# Main.net
KiCad netlist of a schematic drawn in Altium Designer
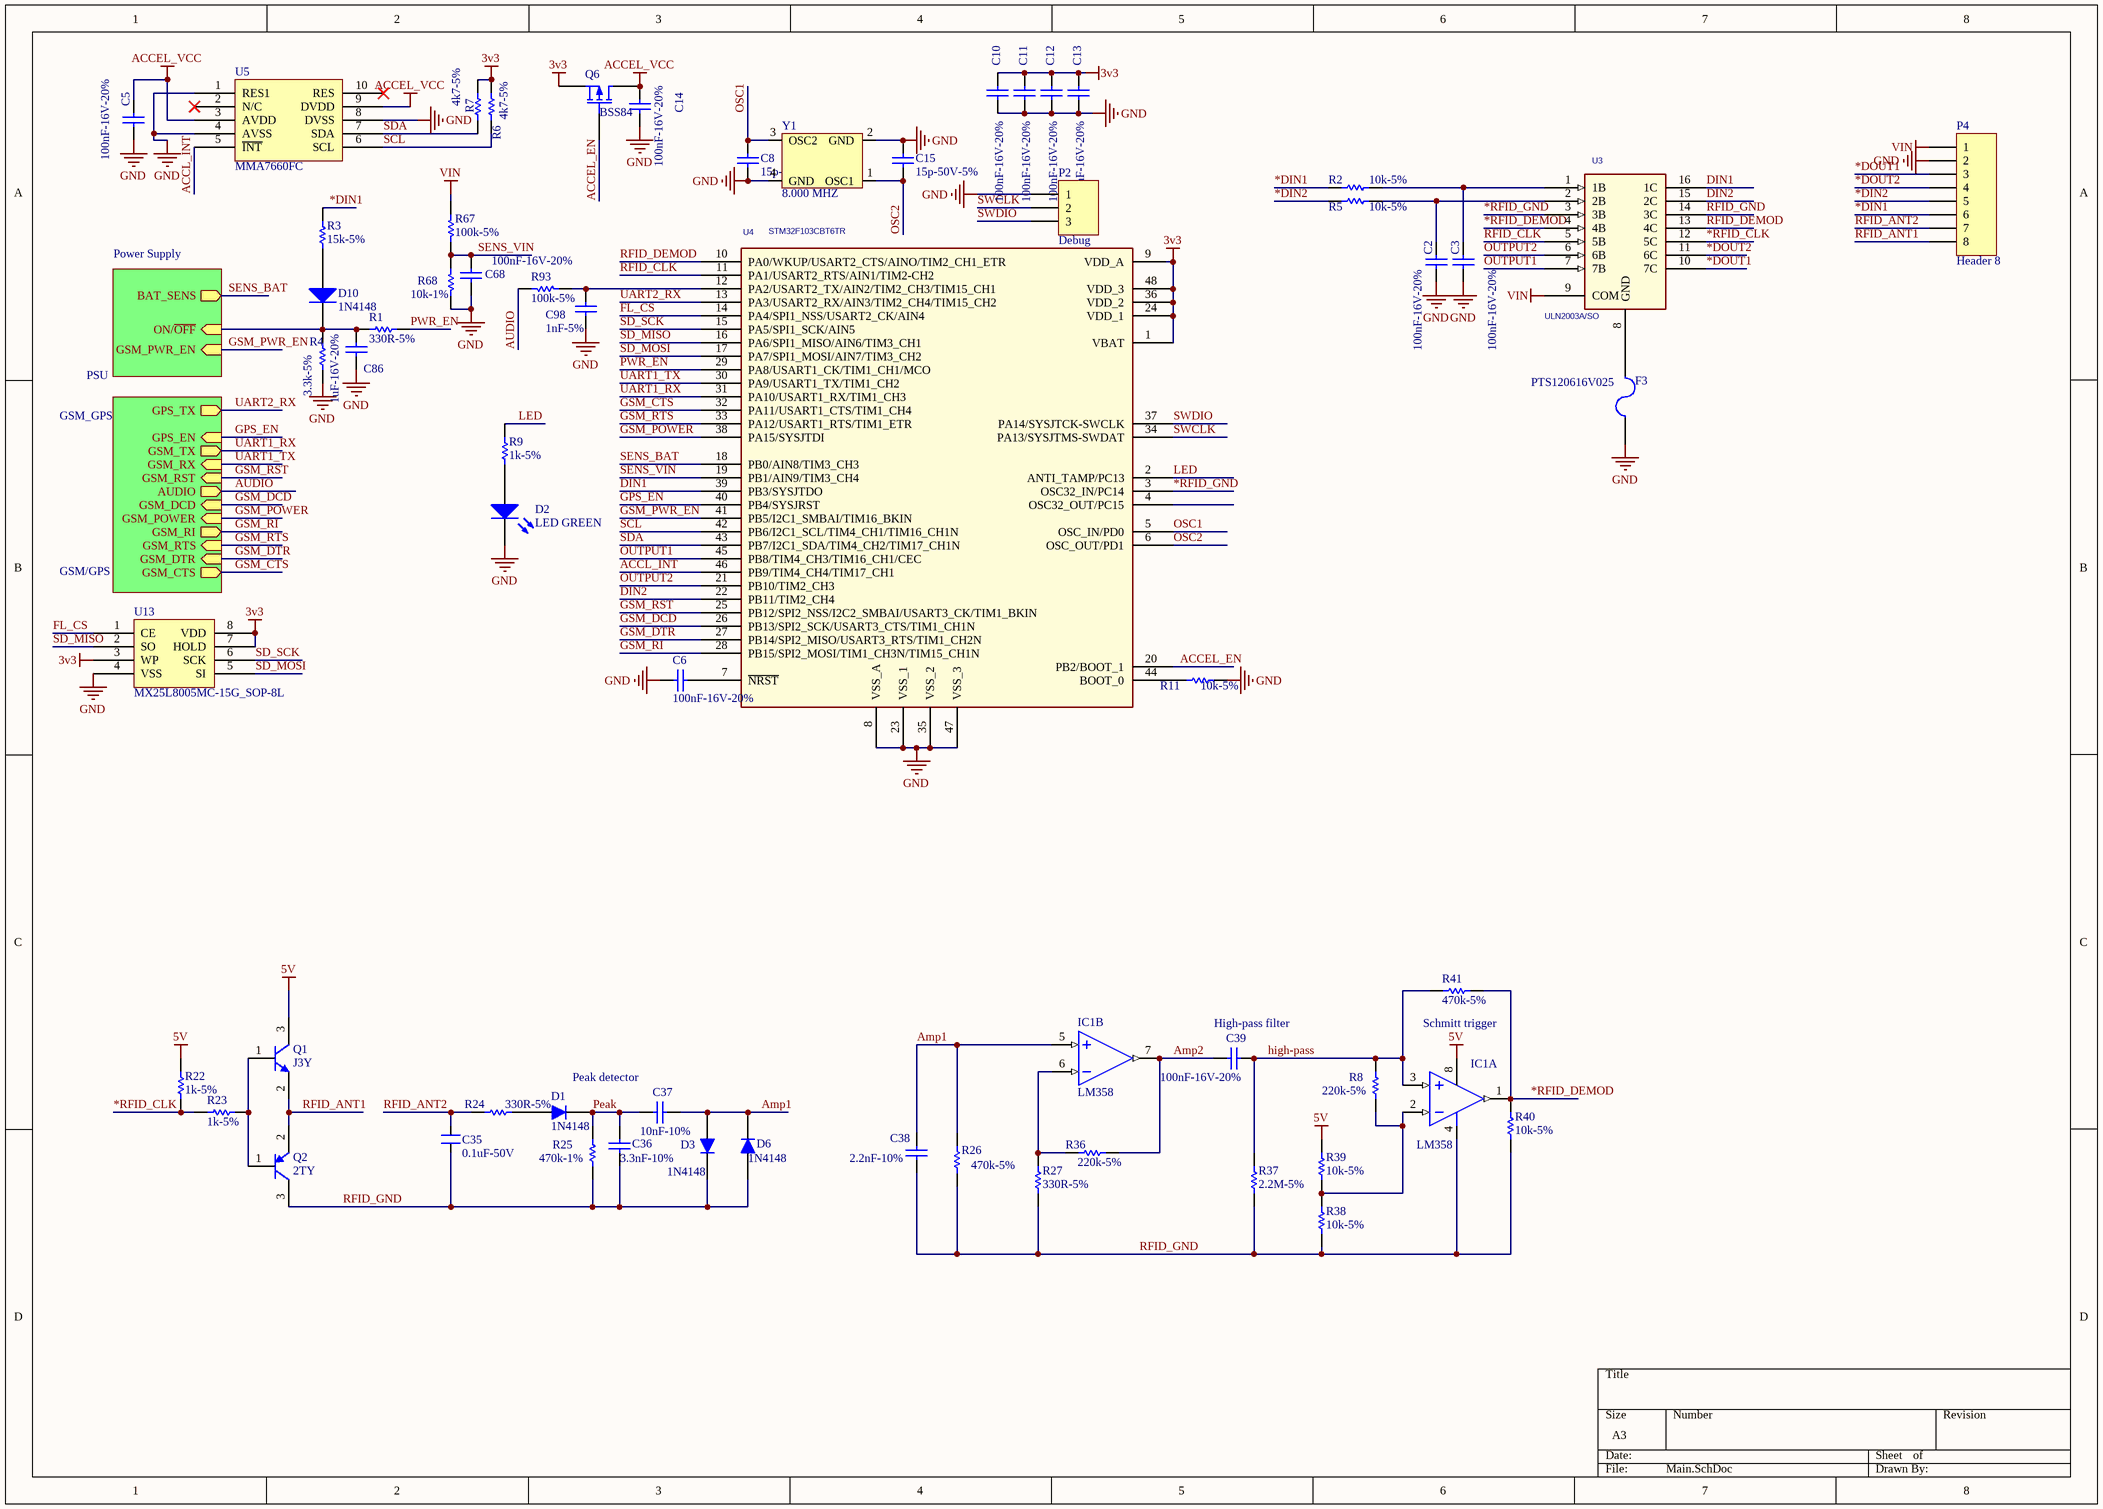
[diagram p0: Main.SchDoc]

(export (version "E")
  (design (tool "Eeschema 10.0.6"))
  (components
    (comp (ref "C2")
      (value "100nF-16V-20%")
      (footprint "0402_TYPE1")
      (description "CAP CER 0.1UF 16V Y5V 0402")
      (fields
        (field (name "MANUFACTURER") "Yageo")
        (field (name "DIGI-KEY PART NUMBER") "311-1047-1-ND")
        (field (name "PUBLISHER") "Altium Limited")
      )
      (libsource (lib "Miscellaneous Devices") (part "Cap"))
    )
    (comp (ref "C3")
      (value "100nF-16V-20%")
      (footprint "0402_TYPE1")
      (description "CAP CER 0.1UF 16V Y5V 0402")
      (fields
        (field (name "MANUFACTURER") "Yageo")
        (field (name "DIGI-KEY PART NUMBER") "311-1047-1-ND")
        (field (name "PUBLISHER") "Altium Limited")
      )
      (libsource (lib "Miscellaneous Devices") (part "Cap"))
    )
    (comp (ref "C5")
      (value "100nF-16V-20%")
      (footprint "0402_TYPE1")
      (description "CAP CER 0.1UF 16V Y5V 0402")
      (fields
        (field (name "MANUFACTURER") "Yageo")
        (field (name "DIGI-KEY PART NUMBER") "311-1047-1-ND")
        (field (name "PUBLISHER") "Altium Limited")
      )
      (libsource (lib "Miscellaneous Devices") (part "Cap"))
    )
    (comp (ref "C6")
      (value "100nF-16V-20%")
      (footprint "0402_TYPE1")
      (description "CAP CER 0.1UF 16V Y5V 0402")
      (fields
        (field (name "MANUFACTURER") "Yageo")
        (field (name "DIGI-KEY PART NUMBER") "311-1047-1-ND")
        (field (name "PUBLISHER") "Altium Limited")
      )
      (libsource (lib "Miscellaneous Devices") (part "Cap"))
    )
    (comp (ref "C8")
      (value "15p-50V-5%")
      (footprint "0402_TYPE1")
      (description "CAP CER 15PF 50V 5% NPO 0402")
      (fields
        (field (name "MANUFACTURER") "Yageo")
        (field (name "DIGI-KEY PART NUMBER") "311-1017-1-ND")
        (field (name "PUBLISHER") "Altium Limited")
      )
      (libsource (lib "Miscellaneous Devices") (part "Cap"))
    )
    (comp (ref "C10")
      (value "100nF-16V-20%")
      (footprint "0402_TYPE1")
      (description "CAP CER 0.1UF 16V Y5V 0402")
      (fields
        (field (name "MANUFACTURER") "Yageo")
        (field (name "DIGI-KEY PART NUMBER") "311-1047-1-ND")
        (field (name "PUBLISHER") "Altium Limited")
      )
      (libsource (lib "Miscellaneous Devices") (part "Cap"))
    )
    (comp (ref "C11")
      (value "100nF-16V-20%")
      (footprint "0402_TYPE1")
      (description "CAP CER 0.1UF 16V Y5V 0402")
      (fields
        (field (name "MANUFACTURER") "Yageo")
        (field (name "DIGI-KEY PART NUMBER") "311-1047-1-ND")
        (field (name "PUBLISHER") "Altium Limited")
      )
      (libsource (lib "Miscellaneous Devices") (part "Cap"))
    )
    (comp (ref "C12")
      (value "100nF-16V-20%")
      (footprint "0402_TYPE1")
      (description "CAP CER 0.1UF 16V Y5V 0402")
      (fields
        (field (name "MANUFACTURER") "Yageo")
        (field (name "DIGI-KEY PART NUMBER") "311-1047-1-ND")
        (field (name "PUBLISHER") "Altium Limited")
      )
      (libsource (lib "Miscellaneous Devices") (part "Cap"))
    )
    (comp (ref "C13")
      (value "100nF-16V-20%")
      (footprint "0402_TYPE1")
      (description "CAP CER 0.1UF 16V Y5V 0402")
      (fields
        (field (name "MANUFACTURER") "Yageo")
        (field (name "DIGI-KEY PART NUMBER") "311-1047-1-ND")
        (field (name "PUBLISHER") "Altium Limited")
      )
      (libsource (lib "Miscellaneous Devices") (part "Cap"))
    )
    (comp (ref "C14")
      (value "100nF-16V-20%")
      (footprint "0402_TYPE1")
      (description "CAP CER 0.1UF 16V Y5V 0402")
      (fields
        (field (name "MANUFACTURER") "Yageo")
        (field (name "DIGI-KEY PART NUMBER") "311-1047-1-ND")
        (field (name "PUBLISHER") "Altium Limited")
      )
      (libsource (lib "Miscellaneous Devices") (part "Cap"))
    )
    (comp (ref "C15")
      (value "15p-50V-5%")
      (footprint "0402_TYPE1")
      (description "CAP CER 15PF 50V 5% NPO 0402")
      (fields
        (field (name "MANUFACTURER") "Yageo")
        (field (name "DIGI-KEY PART NUMBER") "311-1017-1-ND")
        (field (name "PUBLISHER") "Altium Limited")
      )
      (libsource (lib "Miscellaneous Devices") (part "Cap"))
    )
    (comp (ref "C35")
      (value "0.1uF-50V")
      (footprint "C0805 - TYPE3")
      (description "CAP CER 0.1UF 50V Y5V 0603")
      (fields (field (name "DIGI-KEY PART NUMBER") "311-1343-2-ND") (field (name "MANUFACTURER") "Yageo"))
      (libsource (lib "syhaunguyen") (part "CN2"))
    )
    (comp (ref "C36")
      (value "3.3nF-10%")
      (footprint "0402_TYPE1")
      (description "CAP CER 3300PF 50V 10% X7R 0402")
      (fields (field (name "DIGI-KEY PART NUMBER") "311-1034-2-ND") (field (name "MANUFACTURER") "Yageo"))
      (libsource (lib "Capacitor") (part "1nF-50V-C0805"))
    )
    (comp (ref "C37")
      (value "10nF-10%")
      (footprint "0402_TYPE1")
      (description "Non-Polarized Capacitor")
      (fields (field (name "DIGI-KEY PART NUMBER") "CC0402KRX7R9BB103") (field (name "MANUFACTURER") "Yageo"))
      (libsource (lib "Capacitor") (part "10nF-50V-C0805"))
    )
    (comp (ref "C38")
      (value "2.2nF-10%")
      (footprint "0402_TYPE1")
      (description "CAP CER 2200PF 50V 10% X7R 0402")
      (fields (field (name "DIGI-KEY PART NUMBER") "311-1037-2-ND") (field (name "MANUFACTURER") "Yageo"))
      (libsource (lib "Capacitor") (part "2.2nF-50V-C0805"))
    )
    (comp (ref "C39")
      (value "100nF-16V-20%")
      (footprint "0402_TYPE1")
      (description "CAP CER 0.1UF 16V Y5V 0402")
      (fields
        (field (name "MANUFACTURER") "Yageo")
        (field (name "DIGI-KEY PART NUMBER") "311-1047-1-ND")
        (field (name "PUBLISHER") "Altium Limited")
      )
      (libsource (lib "Miscellaneous Devices") (part "Cap"))
    )
    (comp (ref "C68")
      (value "100nF-16V-20%")
      (footprint "0402_TYPE1")
      (description "CAP CER 0.1UF 16V Y5V 0402")
      (fields
        (field (name "MANUFACTURER") "Yageo")
        (field (name "DIGI-KEY PART NUMBER") "311-1047-1-ND")
        (field (name "PUBLISHER") "Altium Limited")
      )
      (libsource (lib "Miscellaneous Devices") (part "Cap"))
    )
    (comp (ref "C86")
      (value "1uF-16V-20%")
      (footprint "0402_TYPE1")
      (description "CAP CER 1UF 16V Y5V 0603")
      (fields
        (field (name "MANUFACTURER") "Yageo")
        (field (name "DIGI-KEY PART NUMBER") "311-1372-1-ND")
        (field (name "PUBLISHER") "Altium Limited")
      )
      (libsource (lib "Miscellaneous Devices") (part "Cap"))
    )
    (comp (ref "C98")
      (value "1nF-5%")
      (footprint "0402_TYPE1")
      (description "Non-Polarized Capacitor")
      (fields (field (name "DIGI-KEY PART NUMBER") "311-1122-1-ND") (field (name "MANUFACTURER") "Yageo"))
      (libsource (lib "Capacitor") (part "1nF-50V-C0805"))
    )
    (comp (ref "D1")
      (value "1N4148")
      (footprint "DO-213AA")
      (description "DIODE SMALL SIG 100V 0.2A ALF2")
      (fields
        (field (name "DIGI-KEY PART NUMBER") "568-1360-1-ND")
        (field (name "MANUFACTURER") "NXP Semiconductors")
      )
      (libsource (lib "Active Components") (part "1N4148"))
    )
    (comp (ref "D2")
      (value "LED GREEN")
      (footprint "LED0603-G")
      (description "LED GREEN CLEAR THIN 0603 SMD")
      (fields
        (field (name "DIGI-KEY PART NUMBER") "160-1446-2-ND")
        (field (name "MANUFACTURER") "Lite-On Inc")
        (field (name "PUBLISHER") "Altium Limited")
      )
      (libsource (lib "Miscellaneous Devices") (part "LED2"))
    )
    (comp (ref "D3")
      (value "1N4148")
      (footprint "DO-213AA")
      (description "DIODE SMALL SIG 100V 0.2A ALF2")
      (fields
        (field (name "DIGI-KEY PART NUMBER") "568-1360-1-ND")
        (field (name "MANUFACTURER") "NXP Semiconductors")
      )
      (libsource (lib "Active Components") (part "1N4148"))
    )
    (comp (ref "D6")
      (value "1N4148")
      (footprint "DO-213AA")
      (description "DIODE SMALL SIG 100V 0.2A ALF2")
      (fields
        (field (name "DIGI-KEY PART NUMBER") "568-1360-1-ND")
        (field (name "MANUFACTURER") "NXP Semiconductors")
      )
      (libsource (lib "Active Components") (part "1N4148"))
    )
    (comp (ref "D10")
      (value "1N4148")
      (footprint "SOD323")
      (description "DIODE SWITCH 75V 200MW SOD323")
      (fields
        (field (name "DIGI-KEY PART NUMBER") "1N4148WS-FDITR-ND")
        (field (name "MANUFACTURER PART NUMBER") "1N4148WS-7-F")
        (field (name "PUBLISHER") "Altium Limited")
      )
      (libsource (lib "Miscellaneous Devices") (part "Diode"))
    )
    (comp (ref "F3")
      (value "PTS120616V025")
      (footprint "PTC1206")
      (description "PTC RESETTABLE SMD 1206 16V .25A")
      (fields
        (field (name "DIGI-KEY PART NUMBER") "283-3137-2-ND")
        (field (name "MANUFACTURER") "Cooper Bussmann")
        (field (name "PUBLISHER") "Altium Limited")
      )
      (libsource (lib "Miscellaneous Devices") (part "Fuse 2"))
    )
    (comp (ref "IC1")
      (value "LM358")
      (footprint "soic8")
      (description "Low-Power Dual Operational Amplifier")
      (libsource (lib "IC") (part "LM358"))
    )
    (comp (ref "P2")
      (value "Debug")
      (footprint "HEADER_1.27mm_3PIN")
      (description "NA")
      (fields (field (name "PUBLISHER") "Altium Limited"))
      (libsource (lib "Miscellaneous Connectors") (part "Header 3"))
    )
    (comp (ref "P4")
      (value "Header 8")
      (footprint "HDR1X8")
      (description "Header, 8-Pin")
      (fields (field (name "PUBLISHER") "Altium Limited"))
      (libsource (lib "Miscellaneous Connectors") (part "Header 8"))
    )
    (comp (ref "Q1")
      (value "J3Y")
      (footprint "SOT23_123")
      (description "NPN Bipolar Transistor")
      (libsource (lib "Active Components") (part "NPN_123"))
    )
    (comp (ref "Q2")
      (value "2TY")
      (footprint "SOT23_123")
      (description "PNP Bipolar Transistor")
      (libsource (lib "Active Components") (part "PNP_123"))
    )
    (comp (ref "Q6")
      (value "BSS84")
      (footprint "SOT23-3")
      (description "MOSFET P-CH 50V 130MA SOT23-3")
      (fields
        (field (name "DIGI-KEY PART NUMBER") "BSS84-FDITR-ND")
        (field (name "MANUFACTURER") "Diodes Inc")
        (field (name "PUBLISHER") "Altium Limited")
      )
      (libsource (lib "Miscellaneous Devices") (part "MOSFET-P"))
    )
    (comp (ref "R1")
      (value "330R-5%")
      (footprint "R0402_TYPE1")
      (description "RES 330 OHM 1/8W 5% 0805 SMD")
      (fields (field (name "DIGI-KEY PART NUMBER") "311-330ARTR-ND") (field (name "MANUFACTURER") "Yageo"))
      (libsource (lib "Resistor") (part "330R-5%-R0805"))
    )
    (comp (ref "R2")
      (value "10k-5%")
      (footprint "R0402_TYPE1")
      (description "RES 10k OHM 1/8W 5% 0805 SMD")
      (fields (field (name "DIGI-KEY PART NUMBER") "311-10KARTR-ND") (field (name "MANUFACTURER") "Yageo"))
      (libsource (lib "Resistor") (part "10k-5%-R0805"))
    )
    (comp (ref "R3")
      (value "15k-5%")
      (footprint "R0402_TYPE1")
      (description "RES 105k OHM 1/4W 1% 0805 SMD")
      (fields (field (name "DIGI-KEY PART NUMBER") "311-105KCRTR-ND") (field (name "MANUFACTURER") "Yageo"))
      (libsource (lib "All_Resistor") (part "105k-1%-R0805"))
    )
    (comp (ref "R4")
      (value "3.3k-5%")
      (footprint "R0402_TYPE1")
      (description "RES 26.1k OHM 1/4W 1% 0805 SMD")
      (fields (field (name "DIGI-KEY PART NUMBER") "311-26.1KCRTR-ND") (field (name "MANUFACTURER") "Yageo"))
      (libsource (lib "All_Resistor") (part "26.1k-1%-R0805"))
    )
    (comp (ref "R5")
      (value "10k-5%")
      (footprint "R0402_TYPE1")
      (description "RES 10k OHM 1/8W 5% 0805 SMD")
      (fields (field (name "DIGI-KEY PART NUMBER") "311-10KARTR-ND") (field (name "MANUFACTURER") "Yageo"))
      (libsource (lib "Resistor") (part "10k-5%-R0805"))
    )
    (comp (ref "R6")
      (value "4k7-5%")
      (footprint "R0402_TYPE1")
      (description "RES 4.7K OHM 1/16W 5% 0402 SMD")
      (fields
        (field (name "DIGI-KEY PART NUMBER") "311-4.7KJRCT-ND")
        (field (name "MANUFACTURER") "Yageo")
        (field (name "PUBLISHER") "Altium Limited")
      )
      (libsource (lib "Miscellaneous Devices") (part "Res1"))
    )
    (comp (ref "R7")
      (value "4k7-5%")
      (footprint "R0402_TYPE1")
      (description "RES 4.7K OHM 1/16W 5% 0402 SMD")
      (fields
        (field (name "DIGI-KEY PART NUMBER") "311-4.7KJRCT-ND")
        (field (name "MANUFACTURER") "Yageo")
        (field (name "PUBLISHER") "Altium Limited")
      )
      (libsource (lib "Miscellaneous Devices") (part "Res1"))
    )
    (comp (ref "R8")
      (value "220k-5%")
      (footprint "R0402_TYPE1")
      (description "RES 220k OHM 1/8W 5% 0805 SMD")
      (fields (field (name "DIGI-KEY PART NUMBER") "311-220KARTR-ND") (field (name "MANUFACTURER") "Yageo"))
      (libsource (lib "Resistor") (part "220k-5%-R0805"))
    )
    (comp (ref "R9")
      (value "1k-5%")
      (footprint "R0402_TYPE1")
      (description "RES 1.0K OHM 1/16W 5% 0402 SMD")
      (fields
        (field (name "DIGI-KEY PART NUMBER") "311-1.0KJRCT-ND")
        (field (name "MANUFACTURER") "Yageo")
        (field (name "PUBLISHER") "Altium Limited")
      )
      (libsource (lib "Miscellaneous Devices") (part "Res1"))
    )
    (comp (ref "R11")
      (value "10k-5%")
      (footprint "R0402_TYPE1")
      (description "RES 10K OHM 1/16W 5% 0402 SMD")
      (fields
        (field (name "DIGI-KEY PART NUMBER") "311-10KJRCT-ND")
        (field (name "MANUFACTURER") "Yageo")
        (field (name "PUBLISHER") "Altium Limited")
      )
      (libsource (lib "Miscellaneous Devices") (part "Res1"))
    )
    (comp (ref "R22")
      (value "1k-5%")
      (footprint "R0402_TYPE1")
      (description "RES 1k OHM 1/8W 5% 0805 SMD")
      (fields (field (name "DIGI-KEY PART NUMBER") "311-1.0KARTR-ND") (field (name "MANUFACTURER") "Yageo"))
      (libsource (lib "All_Resistor") (part "1k-5%-R0805"))
    )
    (comp (ref "R23")
      (value "1k-5%")
      (footprint "R0402_TYPE1")
      (description "RES 1k OHM 1/8W 5% 0805 SMD")
      (fields (field (name "DIGI-KEY PART NUMBER") "311-1.0KARTR-ND") (field (name "MANUFACTURER") "Yageo"))
      (libsource (lib "All_Resistor") (part "1k-5%-R0805"))
    )
    (comp (ref "R24")
      (value "330R-5%")
      (footprint "R0402_TYPE1")
      (description "RES 330 OHM 1/8W 5% 0805 SMD")
      (fields (field (name "DIGI-KEY PART NUMBER") "311-330ARTR-ND") (field (name "MANUFACTURER") "Yageo"))
      (libsource (lib "Resistor") (part "330k-5%-R0805"))
    )
    (comp (ref "R25")
      (value "470k-1%")
      (footprint "R0402_TYPE1")
      (description "RES 470k OHM 1/4W 1% 0805 SMD")
      (fields (field (name "DIGI-KEY PART NUMBER") "311-470KCRTR-ND") (field (name "MANUFACTURER") "Yageo"))
      (libsource (lib "Resistor") (part "470k-1%-R0805"))
    )
    (comp (ref "R26")
      (value "470k-5%")
      (footprint "R0402_TYPE1")
      (description "RES 470k OHM 1/8W 5% 0805 SMD")
      (fields (field (name "DIGI-KEY PART NUMBER") "311-470KARTR-ND") (field (name "MANUFACTURER") "Yageo"))
      (libsource (lib "Resistor") (part "470k-5%-R0805"))
    )
    (comp (ref "R27")
      (value "330R-5%")
      (footprint "R0402_TYPE1")
      (description "RES 330 OHM 1/8W 5% 0805 SMD")
      (fields (field (name "DIGI-KEY PART NUMBER") "311-330ARTR-ND") (field (name "MANUFACTURER") "Yageo"))
      (libsource (lib "Resistor") (part "330R-5%-R0805"))
    )
    (comp (ref "R36")
      (value "220k-5%")
      (footprint "R0402_TYPE1")
      (description "RES 220k OHM 1/8W 5% 0805 SMD")
      (fields (field (name "DIGI-KEY PART NUMBER") "311-220KARTR-ND") (field (name "MANUFACTURER") "Yageo"))
      (libsource (lib "Resistor") (part "220k-5%-R0805"))
    )
    (comp (ref "R37")
      (value "2.2M-5%")
      (footprint "R0402_TYPE1")
      (description "RES 2.2M OHM 1/8W 5% 0805 SMD")
      (fields (field (name "DIGI-KEY PART NUMBER") "311-2.2MARTR-ND") (field (name "MANUFACTURER") "Yageo"))
      (libsource (lib "Resistor") (part "2.2M-5%-R0805"))
    )
    (comp (ref "R38")
      (value "10k-5%")
      (footprint "R0402_TYPE1")
      (description "RES 10k OHM 1/8W 5% 0805 SMD")
      (fields (field (name "DIGI-KEY PART NUMBER") "311-10KARTR-ND") (field (name "MANUFACTURER") "Yageo"))
      (libsource (lib "Resistor") (part "10k-5%-R0805"))
    )
    (comp (ref "R39")
      (value "10k-5%")
      (footprint "R0402_TYPE1")
      (description "RES 10k OHM 1/8W 5% 0805 SMD")
      (fields (field (name "DIGI-KEY PART NUMBER") "311-10KARTR-ND") (field (name "MANUFACTURER") "Yageo"))
      (libsource (lib "Resistor") (part "10k-5%-R0805"))
    )
    (comp (ref "R40")
      (value "10k-5%")
      (footprint "R0402_TYPE1")
      (description "RES 10k OHM 1/8W 5% 0805 SMD")
      (fields (field (name "DIGI-KEY PART NUMBER") "311-10KARTR-ND") (field (name "MANUFACTURER") "Yageo"))
      (libsource (lib "Resistor") (part "10k-5%-R0805"))
    )
    (comp (ref "R41")
      (value "470k-5%")
      (footprint "R0402_TYPE1")
      (description "RES 470k OHM 1/8W 5% 0805 SMD")
      (fields (field (name "DIGI-KEY PART NUMBER") "311-470KARTR-ND") (field (name "MANUFACTURER") "Yageo"))
      (libsource (lib "Resistor") (part "470k-5%-R0805"))
    )
    (comp (ref "R67")
      (value "100k-5%")
      (footprint "R0402_TYPE1")
      (description "RES 100K OHM 1/16W 5% 0402 SMD")
      (fields
        (field (name "DIGI-KEY PART NUMBER") "311-100KJRCT-ND")
        (field (name "MANUFACTURER") "Yageo")
        (field (name "PUBLISHER") "Altium Limited")
      )
      (libsource (lib "Miscellaneous Devices") (part "Res1"))
    )
    (comp (ref "R68")
      (value "10k-1%")
      (footprint "R0402_TYPE1")
      (description "RES 10.0K OHM 1/16W 1% 0402 SMD")
      (fields
        (field (name "DIGI-KEY PART NUMBER") "311-10.0KLRTR-ND")
        (field (name "MANUFACTURER") "Yageo")
        (field (name "PUBLISHER") "Altium Limited")
      )
      (libsource (lib "Miscellaneous Devices") (part "Res1"))
    )
    (comp (ref "R93")
      (value "100k-5%")
      (footprint "R0402_TYPE1")
      (description "RES 100K OHM 1/16W 5% 0402 SMD")
      (fields
        (field (name "DIGI-KEY PART NUMBER") "311-100KJRCT-ND")
        (field (name "MANUFACTURER") "Yageo")
        (field (name "PUBLISHER") "Altium Limited")
      )
      (libsource (lib "") (part "Res1_1"))
    )
    (comp (ref "U3")
      (value "ULN2003A/SO")
      (footprint "SO16-150mil")
      (description "IC DARL TRANS ARRAY 16-SOIC")
      (fields
        (field (name "DIGI-KEY PART NUMBER") "296-1368-2-ND")
        (field (name "MANUFACTURER PART NUMBER") "ULN2003ADR")
      )
      (libsource (lib "*") (part "ULN2003A/SO_0"))
    )
    (comp (ref "U4")
      (value "STM32F103CBT6TR")
      (footprint "TQFP-48-P0.5")
      (description "MCU ARM 128K FLASH/TIMER")
      (fields
        (field (name "DIGI-KEY PART NUMBER") "497-6288-ND")
        (field (name "MANUFACTURER") "STMicroelectronics")
      )
      (libsource (lib "*") (part "ATmega128_4"))
    )
    (comp (ref "U5")
      (value "MMA7660FC")
      (footprint "MMA7660FC")
      (description "ACCELEROMETER 3X3 DGTL 10-DFN")
      (fields
        (field (name "DIGI-KEY PART NUMBER") "MMA7660FCT-ND")
        (field (name "MANUFACTURER") "Freescale Semiconductor")
      )
      (libsource (lib "Lib") (part "MMA7660FC"))
    )
    (comp (ref "U13")
      (value "MX25L8005MC-15G_SOP-8L")
      (footprint "SO8-200mil")
      (fields (field (name "MANUFACTURER") "Tyrone"))
      (libsource (lib "My LB") (part "FlashIC"))
    )
    (comp (ref "Y1")
      (value "8.000 MHZ")
      (footprint "SMD CRYSTAL 4 x 2.5")
      (description "CRYSTAL 8.000 MHZ 18PF SMD")
      (fields
        (field (name "DIGI-KEY PART NUMBER") "887-1452-2-ND")
        (field (name "MANUFACTURER") "TXC CORPORATION")
      )
      (libsource (lib "Schlib1") (part "CRYSTAL-SMT"))
    )
  )
  (nets
    (net (code "1") (name "/*DIN1") (class "Default")
      (node (ref "P4") (pin "6") (pinfunction "6_6") (pintype "passive"))
      (node (ref "R2") (pin "2") (pinfunction "2_2") (pintype "passive"))
      (node (ref "R3") (pin "2") (pinfunction "2_2") (pintype "passive"))
    )
    (net (code "2") (name "/*DIN2") (class "Default")
      (node (ref "P4") (pin "5") (pinfunction "5_5") (pintype "passive"))
      (node (ref "R5") (pin "2") (pinfunction "2_2") (pintype "passive"))
    )
    (net (code "3") (name "/*DOUT1") (class "Default")
      (node (ref "P4") (pin "3") (pinfunction "3_3") (pintype "passive"))
      (node (ref "U3") (pin "10") (pinfunction "7C_10") (pintype "open_collector"))
    )
    (net (code "4") (name "/*DOUT2") (class "Default")
      (node (ref "P4") (pin "4") (pinfunction "4_4") (pintype "passive"))
      (node (ref "U3") (pin "11") (pinfunction "6C_11") (pintype "open_collector"))
    )
    (net (code "5") (name "/*RFID_CLK") (class "Default")
      (node (ref "R22") (pin "1") (pinfunction "1_1") (pintype "passive"))
      (node (ref "R23") (pin "2") (pinfunction "2_2") (pintype "passive"))
      (node (ref "U3") (pin "12") (pinfunction "5C_12") (pintype "open_collector"))
    )
    (net (code "6") (name "/*RFID_DEMOD") (class "Default")
      (node (ref "IC1") (pin "1") (pinfunction "OUT_1") (pintype "output"))
      (node (ref "R40") (pin "2") (pinfunction "2_2") (pintype "passive"))
      (node (ref "R41") (pin "1") (pinfunction "1_1") (pintype "passive"))
      (node (ref "U3") (pin "4") (pinfunction "4B_4") (pintype "input"))
    )
    (net (code "7") (name "/*RFID_GND") (class "Default")
      (node (ref "U3") (pin "3") (pinfunction "3B_3") (pintype "input"))
      (node (ref "U4") (pin "3") (pinfunction "OSC32_IN/PC14_3") (pintype "passive"))
    )
    (net (code "8") (name "/ACCEL_EN") (class "Default")
      (node (ref "Q6") (pin "1") (pinfunction "G_1") (pintype "passive"))
      (node (ref "U4") (pin "20") (pinfunction "PB2/BOOT_1_20") (pintype "passive"))
    )
    (net (code "9") (name "/ACCL_INT") (class "Default")
      (node (ref "U4") (pin "46") (pinfunction "PB9/TIM4_CH4/TIM17_CH1_46") (pintype "passive"))
      (node (ref "U5") (pin "5") (pinfunction "~{INT}_5") (pintype "passive"))
    )
    (net (code "10") (name "/AUDIO") (class "Default")
      (node (ref "R93") (pin "1") (pinfunction "1_1") (pintype "passive"))
    )
    (net (code "11") (name "/Amp1") (class "Default")
      (node (ref "C37") (pin "2") (pinfunction "2_2") (pintype "passive"))
      (node (ref "C38") (pin "2") (pinfunction "2_2") (pintype "passive"))
      (node (ref "D3") (pin "1") (pinfunction "A_1") (pintype "passive"))
      (node (ref "D6") (pin "2") (pinfunction "K_2") (pintype "passive"))
      (node (ref "IC1") (pin "5") (pinfunction "IN+_5") (pintype "input"))
      (node (ref "R26") (pin "1") (pinfunction "1_1") (pintype "passive"))
    )
    (net (code "12") (name "/Amp2") (class "Default")
      (node (ref "C39") (pin "2") (pinfunction "2_2") (pintype "passive"))
      (node (ref "IC1") (pin "7") (pinfunction "OUT_7") (pintype "output"))
      (node (ref "R36") (pin "1") (pinfunction "1_1") (pintype "passive"))
    )
    (net (code "13") (name "/DIN1") (class "Default")
      (node (ref "U3") (pin "16") (pinfunction "1C_16") (pintype "open_collector"))
      (node (ref "U4") (pin "39") (pinfunction "PB3/SYSJTDO_39") (pintype "passive"))
    )
    (net (code "14") (name "/DIN2") (class "Default")
      (node (ref "U3") (pin "15") (pinfunction "2C_15") (pintype "open_collector"))
      (node (ref "U4") (pin "22") (pinfunction "PB11/TIM2_CH4_22") (pintype "passive"))
    )
    (net (code "15") (name "/FL_CS") (class "Default")
      (node (ref "U13") (pin "1") (pinfunction "CE_1") (pintype "passive"))
      (node (ref "U4") (pin "14") (pinfunction "PA4/SPI1_NSS/USART2_CK/AIN4_14") (pintype "passive"))
    )
    (net (code "16") (name "/GPS_EN") (class "Default")
      (node (ref "U4") (pin "40") (pinfunction "PB4/SYSJRST_40") (pintype "passive"))
    )
    (net (code "17") (name "/GSM_CTS") (class "Default")
      (node (ref "U4") (pin "32") (pinfunction "PA11/USART1_CTS/TIM1_CH4_32") (pintype "passive"))
    )
    (net (code "18") (name "/GSM_DCD") (class "Default")
      (node (ref "U4") (pin "26") (pinfunction "PB13/SPI2_SCK/USART3_CTS/TIM1_CH1N_26") (pintype "passive"))
    )
    (net (code "19") (name "/GSM_DTR") (class "Default")
      (node (ref "U4") (pin "27") (pinfunction "PB14/SPI2_MISO/USART3_RTS/TIM1_CH2N_27") (pintype "passive"))
    )
    (net (code "20") (name "/GSM_POWER") (class "Default")
      (node (ref "U4") (pin "38") (pinfunction "PA15/SYSJTDI_38") (pintype "passive"))
    )
    (net (code "21") (name "/GSM_PWR_EN") (class "Default")
      (node (ref "U4") (pin "41") (pinfunction "PB5/I2C1_SMBAI/TIM16_BKIN_41") (pintype "passive"))
    )
    (net (code "22") (name "/GSM_RI") (class "Default")
      (node (ref "U4") (pin "28") (pinfunction "PB15/SPI2_MOSI/TIM1_CH3N/TIM15_CH1N_28") (pintype "passive"))
    )
    (net (code "23") (name "/GSM_RST") (class "Default")
      (node (ref "U4") (pin "25") (pinfunction "PB12/SPI2_NSS/I2C2_SMBAI/USART3_CK/TIM1_BKIN_25") (pintype "passive"))
    )
    (net (code "24") (name "/GSM_RTS") (class "Default")
      (node (ref "U4") (pin "33") (pinfunction "PA12/USART1_RTS/TIM1_ETR_33") (pintype "passive"))
    )
    (net (code "25") (name "/LED") (class "Default")
      (node (ref "R9") (pin "2") (pinfunction "2_2") (pintype "passive"))
      (node (ref "U4") (pin "2") (pinfunction "ANTI_TAMP/PC13_2") (pintype "passive"))
    )
    (net (code "26") (name "/ON{slash}~{OFF}") (class "Default")
      (node (ref "C86") (pin "2") (pinfunction "2_2") (pintype "passive"))
      (node (ref "D10") (pin "2") (pinfunction "K_2") (pintype "passive"))
      (node (ref "R1") (pin "2") (pinfunction "2_2") (pintype "passive"))
      (node (ref "R4") (pin "2") (pinfunction "2_2") (pintype "passive"))
    )
    (net (code "27") (name "/OSC1") (class "Default")
      (node (ref "C8") (pin "2") (pinfunction "2_2") (pintype "passive"))
      (node (ref "U4") (pin "5") (pinfunction "OSC_IN/PD0_5") (pintype "passive"))
      (node (ref "Y1") (pin "3") (pinfunction "OSC2_3") (pintype "passive"))
    )
    (net (code "28") (name "/OSC2") (class "Default")
      (node (ref "C15") (pin "1") (pinfunction "1_1") (pintype "passive"))
      (node (ref "U4") (pin "6") (pinfunction "OSC_OUT/PD1_6") (pintype "passive"))
      (node (ref "Y1") (pin "1") (pinfunction "OSC1_1") (pintype "passive"))
    )
    (net (code "29") (name "/OUTPUT1") (class "Default")
      (node (ref "U3") (pin "7") (pinfunction "7B_7") (pintype "input"))
      (node (ref "U4") (pin "45") (pinfunction "PB8/TIM4_CH3/TIM16_CH1/CEC_45") (pintype "passive"))
    )
    (net (code "30") (name "/OUTPUT2") (class "Default")
      (node (ref "U3") (pin "6") (pinfunction "6B_6") (pintype "input"))
      (node (ref "U4") (pin "21") (pinfunction "PB10/TIM2_CH3_21") (pintype "passive"))
    )
    (net (code "31") (name "/PWR_EN") (class "Default")
      (node (ref "R1") (pin "1") (pinfunction "1_1") (pintype "passive"))
      (node (ref "U4") (pin "29") (pinfunction "PA8/USART1_CK/TIM1_CH1/MCO_29") (pintype "passive"))
    )
    (net (code "32") (name "/Peak") (class "Default")
      (node (ref "C36") (pin "1") (pinfunction "1_1") (pintype "passive"))
      (node (ref "C37") (pin "1") (pinfunction "1_1") (pintype "passive"))
      (node (ref "D1") (pin "2") (pinfunction "K_2") (pintype "passive"))
      (node (ref "R25") (pin "1") (pinfunction "1_1") (pintype "passive"))
    )
    (net (code "33") (name "/RFID_ANT1") (class "Default")
      (node (ref "P4") (pin "8") (pinfunction "8_8") (pintype "passive"))
      (node (ref "Q1") (pin "2") (pinfunction "E_2") (pintype "passive"))
      (node (ref "Q2") (pin "2") (pinfunction "E_2") (pintype "passive"))
    )
    (net (code "34") (name "/RFID_ANT2") (class "Default")
      (node (ref "C35") (pin "2") (pinfunction "2_2") (pintype "passive"))
      (node (ref "P4") (pin "7") (pinfunction "7_7") (pintype "passive"))
      (node (ref "R24") (pin "2") (pinfunction "2_2") (pintype "passive"))
    )
    (net (code "35") (name "/RFID_CLK") (class "Default")
      (node (ref "U3") (pin "5") (pinfunction "5B_5") (pintype "input"))
      (node (ref "U4") (pin "11") (pinfunction "PA1/USART2_RTS/AIN1/TIM2-CH2_11") (pintype "passive"))
    )
    (net (code "36") (name "/RFID_DEMOD") (class "Default")
      (node (ref "U3") (pin "13") (pinfunction "4C_13") (pintype "open_collector"))
      (node (ref "U4") (pin "10") (pinfunction "PA0/WKUP/USART2_CTS/AINO/TIM2_CH1_ETR_10") (pintype "passive"))
    )
    (net (code "37") (name "/RFID_GND") (class "Default")
      (node (ref "C35") (pin "1") (pinfunction "1_1") (pintype "passive"))
      (node (ref "C36") (pin "2") (pinfunction "2_2") (pintype "passive"))
      (node (ref "C38") (pin "1") (pinfunction "1_1") (pintype "passive"))
      (node (ref "D3") (pin "2") (pinfunction "K_2") (pintype "passive"))
      (node (ref "D6") (pin "1") (pinfunction "A_1") (pintype "passive"))
      (node (ref "IC1") (pin "4") (pinfunction "-V_4") (pintype "passive"))
      (node (ref "Q2") (pin "3") (pinfunction "C_3") (pintype "passive"))
      (node (ref "R25") (pin "2") (pinfunction "2_2") (pintype "passive"))
      (node (ref "R26") (pin "2") (pinfunction "2_2") (pintype "passive"))
      (node (ref "R27") (pin "1") (pinfunction "1_1") (pintype "passive"))
      (node (ref "R37") (pin "1") (pinfunction "1_1") (pintype "passive"))
      (node (ref "R38") (pin "2") (pinfunction "2_2") (pintype "passive"))
      (node (ref "R40") (pin "1") (pinfunction "1_1") (pintype "passive"))
      (node (ref "U3") (pin "14") (pinfunction "3C_14") (pintype "open_collector"))
    )
    (net (code "38") (name "/SCL") (class "Default")
      (node (ref "R6") (pin "1") (pinfunction "1_1") (pintype "passive"))
      (node (ref "U4") (pin "42") (pinfunction "PB6/I2C1_SCL/TIM4_CH1/TIM16_CH1N_42") (pintype "passive"))
      (node (ref "U5") (pin "6") (pinfunction "SCL_6") (pintype "passive"))
    )
    (net (code "39") (name "/SDA") (class "Default")
      (node (ref "R7") (pin "1") (pinfunction "1_1") (pintype "passive"))
      (node (ref "U4") (pin "43") (pinfunction "PB7/I2C1_SDA/TIM4_CH2/TIM17_CH1N_43") (pintype "passive"))
      (node (ref "U5") (pin "7") (pinfunction "SDA_7") (pintype "passive"))
    )
    (net (code "40") (name "/SD_MISO") (class "Default")
      (node (ref "U13") (pin "2") (pinfunction "SO_2") (pintype "passive"))
      (node (ref "U4") (pin "16") (pinfunction "PA6/SPI1_MISO/AIN6/TIM3_CH1_16") (pintype "passive"))
    )
    (net (code "41") (name "/SD_MOSI") (class "Default")
      (node (ref "U13") (pin "5") (pinfunction "SI_5") (pintype "passive"))
      (node (ref "U4") (pin "17") (pinfunction "PA7/SPI1_MOSI/AIN7/TIM3_CH2_17") (pintype "passive"))
    )
    (net (code "42") (name "/SD_SCK") (class "Default")
      (node (ref "U13") (pin "6") (pinfunction "SCK_6") (pintype "passive"))
      (node (ref "U4") (pin "15") (pinfunction "PA5/SPI1_SCK/AIN5_15") (pintype "passive"))
    )
    (net (code "43") (name "/SENS_BAT") (class "Default")
      (node (ref "U4") (pin "18") (pinfunction "PB0/AIN8/TIM3_CH3_18") (pintype "passive"))
    )
    (net (code "44") (name "/SENS_VIN") (class "Default")
      (node (ref "C68") (pin "2") (pinfunction "2_2") (pintype "passive"))
      (node (ref "R67") (pin "2") (pinfunction "2_2") (pintype "passive"))
      (node (ref "R68") (pin "2") (pinfunction "2_2") (pintype "passive"))
      (node (ref "U4") (pin "19") (pinfunction "PB1/AIN9/TIM3_CH4_19") (pintype "passive"))
    )
    (net (code "45") (name "/SWCLK") (class "Default")
      (node (ref "P2") (pin "2") (pinfunction "2_2") (pintype "passive"))
      (node (ref "U4") (pin "34") (pinfunction "PA13/SYSJTMS-SWDAT_34") (pintype "passive"))
    )
    (net (code "46") (name "/SWDIO") (class "Default")
      (node (ref "P2") (pin "3") (pinfunction "3_3") (pintype "passive"))
      (node (ref "U4") (pin "37") (pinfunction "PA14/SYSJTCK-SWCLK_37") (pintype "passive"))
    )
    (net (code "47") (name "/UART1_RX") (class "Default")
      (node (ref "U4") (pin "31") (pinfunction "PA10/USART1_RX/TIM1_CH3_31") (pintype "passive"))
    )
    (net (code "48") (name "/UART1_TX") (class "Default")
      (node (ref "U4") (pin "30") (pinfunction "PA9/USART1_TX/TIM1_CH2_30") (pintype "passive"))
    )
    (net (code "49") (name "/UART2_RX") (class "Default")
      (node (ref "U4") (pin "13") (pinfunction "PA3/USART2_RX/AIN3/TIM2_CH4/TIM15_CH2_13") (pintype "passive"))
    )
    (net (code "50") (name "/high-pass") (class "Default")
      (node (ref "C39") (pin "1") (pinfunction "1_1") (pintype "passive"))
      (node (ref "IC1") (pin "3") (pinfunction "IN+_3") (pintype "input"))
      (node (ref "R37") (pin "2") (pinfunction "2_2") (pintype "passive"))
      (node (ref "R41") (pin "2") (pinfunction "2_2") (pintype "passive"))
      (node (ref "R8") (pin "2") (pinfunction "2_2") (pintype "passive"))
    )
    (net (code "51") (name "3v3") (class "Default")
      (node (ref "C10") (pin "1") (pinfunction "1_1") (pintype "passive"))
      (node (ref "C11") (pin "1") (pinfunction "1_1") (pintype "passive"))
      (node (ref "C12") (pin "1") (pinfunction "1_1") (pintype "passive"))
      (node (ref "C13") (pin "1") (pinfunction "1_1") (pintype "passive"))
      (node (ref "Q6") (pin "2") (pinfunction "S_2") (pintype "passive"))
      (node (ref "R6") (pin "2") (pinfunction "2_2") (pintype "passive"))
      (node (ref "R7") (pin "2") (pinfunction "2_2") (pintype "passive"))
      (node (ref "U13") (pin "3") (pinfunction "WP_3") (pintype "passive"))
      (node (ref "U13") (pin "7") (pinfunction "HOLD_7") (pintype "passive"))
      (node (ref "U13") (pin "8") (pinfunction "VDD_8") (pintype "passive"))
      (node (ref "U4") (pin "1") (pinfunction "VBAT_1") (pintype "passive"))
      (node (ref "U4") (pin "24") (pinfunction "VDD_1_24") (pintype "passive"))
      (node (ref "U4") (pin "36") (pinfunction "VDD_2_36") (pintype "passive"))
      (node (ref "U4") (pin "48") (pinfunction "VDD_3_48") (pintype "passive"))
      (node (ref "U4") (pin "9") (pinfunction "VDD_A_9") (pintype "passive"))
    )
    (net (code "52") (name "5V") (class "Default")
      (node (ref "IC1") (pin "8") (pinfunction "+V_8") (pintype "passive"))
      (node (ref "Q1") (pin "3") (pinfunction "C_3") (pintype "passive"))
      (node (ref "R22") (pin "2") (pinfunction "2_2") (pintype "passive"))
      (node (ref "R39") (pin "1") (pinfunction "1_1") (pintype "passive"))
    )
    (net (code "53") (name "ACCEL_VCC") (class "Default")
      (node (ref "C14") (pin "2") (pinfunction "2_2") (pintype "passive"))
      (node (ref "C5") (pin "2") (pinfunction "2_2") (pintype "passive"))
      (node (ref "Q6") (pin "3") (pinfunction "D_3") (pintype "passive"))
      (node (ref "U5") (pin "3") (pinfunction "AVDD_3") (pintype "passive"))
      (node (ref "U5") (pin "9") (pinfunction "DVDD_9") (pintype "passive"))
    )
    (net (code "54") (name "GND") (class "Default")
      (node (ref "C10") (pin "2") (pinfunction "2_2") (pintype "passive"))
      (node (ref "C11") (pin "2") (pinfunction "2_2") (pintype "passive"))
      (node (ref "C12") (pin "2") (pinfunction "2_2") (pintype "passive"))
      (node (ref "C13") (pin "2") (pinfunction "2_2") (pintype "passive"))
      (node (ref "C14") (pin "1") (pinfunction "1_1") (pintype "passive"))
      (node (ref "C15") (pin "2") (pinfunction "2_2") (pintype "passive"))
      (node (ref "C2") (pin "2") (pinfunction "2_2") (pintype "passive"))
      (node (ref "C3") (pin "2") (pinfunction "2_2") (pintype "passive"))
      (node (ref "C5") (pin "1") (pinfunction "1_1") (pintype "passive"))
      (node (ref "C6") (pin "2") (pinfunction "2_2") (pintype "passive"))
      (node (ref "C68") (pin "1") (pinfunction "1_1") (pintype "passive"))
      (node (ref "C8") (pin "1") (pinfunction "1_1") (pintype "passive"))
      (node (ref "C86") (pin "1") (pinfunction "1_1") (pintype "passive"))
      (node (ref "C98") (pin "1") (pinfunction "1_1") (pintype "passive"))
      (node (ref "D2") (pin "2") (pinfunction "K_2") (pintype "passive"))
      (node (ref "F3") (pin "2") (pinfunction "2_2") (pintype "passive"))
      (node (ref "P2") (pin "1") (pinfunction "1_1") (pintype "passive"))
      (node (ref "P4") (pin "2") (pinfunction "2_2") (pintype "passive"))
      (node (ref "R11") (pin "1") (pinfunction "1_1") (pintype "passive"))
      (node (ref "R4") (pin "1") (pinfunction "1_1") (pintype "passive"))
      (node (ref "R68") (pin "1") (pinfunction "1_1") (pintype "passive"))
      (node (ref "U13") (pin "4") (pinfunction "VSS_4") (pintype "passive"))
      (node (ref "U4") (pin "23") (pinfunction "VSS_1_23") (pintype "passive"))
      (node (ref "U4") (pin "35") (pinfunction "VSS_2_35") (pintype "passive"))
      (node (ref "U4") (pin "47") (pinfunction "VSS_3_47") (pintype "passive"))
      (node (ref "U4") (pin "8") (pinfunction "VSS_A_8") (pintype "passive"))
      (node (ref "U5") (pin "1") (pinfunction "RES1_1") (pintype "passive"))
      (node (ref "U5") (pin "4") (pinfunction "AVSS_4") (pintype "passive"))
      (node (ref "U5") (pin "8") (pinfunction "DVSS_8") (pintype "passive"))
      (node (ref "Y1") (pin "2") (pinfunction "GND_2") (pintype "passive"))
      (node (ref "Y1") (pin "4") (pinfunction "GND_4") (pintype "passive"))
    )
    (net (code "55") (name "Net-(D1-A)") (class "Default")
      (node (ref "D1") (pin "1") (pinfunction "A_1") (pintype "passive"))
      (node (ref "R24") (pin "1") (pinfunction "1_1") (pintype "passive"))
    )
    (net (code "56") (name "Net-(D2-A)") (class "Default")
      (node (ref "D2") (pin "1") (pinfunction "A_1") (pintype "passive"))
      (node (ref "R9") (pin "1") (pinfunction "1_1") (pintype "passive"))
    )
    (net (code "57") (name "Net-(D10-A)") (class "Default")
      (node (ref "D10") (pin "1") (pinfunction "A_1") (pintype "passive"))
      (node (ref "R3") (pin "1") (pinfunction "1_1") (pintype "passive"))
    )
    (net (code "58") (name "Net-(IC1A-IN-)") (class "Default")
      (node (ref "IC1") (pin "2") (pinfunction "IN-_2") (pintype "input"))
      (node (ref "R38") (pin "1") (pinfunction "1_1") (pintype "passive"))
      (node (ref "R39") (pin "2") (pinfunction "2_2") (pintype "passive"))
      (node (ref "R8") (pin "1") (pinfunction "1_1") (pintype "passive"))
    )
    (net (code "59") (name "Net-(IC1B-IN-)") (class "Default")
      (node (ref "IC1") (pin "6") (pinfunction "IN-_6") (pintype "input"))
      (node (ref "R27") (pin "2") (pinfunction "2_2") (pintype "passive"))
      (node (ref "R36") (pin "2") (pinfunction "2_2") (pintype "passive"))
    )
    (net (code "60") (name "Net-(Q1-B)") (class "Default")
      (node (ref "Q1") (pin "1") (pinfunction "B_1") (pintype "passive"))
      (node (ref "Q2") (pin "1") (pinfunction "B_1") (pintype "passive"))
      (node (ref "R23") (pin "1") (pinfunction "1_1") (pintype "passive"))
    )
    (net (code "61") (name "Net-(U3-1B)") (class "Default")
      (node (ref "C3") (pin "1") (pinfunction "1_1") (pintype "passive"))
      (node (ref "R2") (pin "1") (pinfunction "1_1") (pintype "passive"))
      (node (ref "U3") (pin "1") (pinfunction "1B_1") (pintype "input"))
    )
    (net (code "62") (name "Net-(U3-2B)") (class "Default")
      (node (ref "C2") (pin "1") (pinfunction "1_1") (pintype "passive"))
      (node (ref "R5") (pin "1") (pinfunction "1_1") (pintype "passive"))
      (node (ref "U3") (pin "2") (pinfunction "2B_2") (pintype "input"))
    )
    (net (code "63") (name "Net-(U3-GND)") (class "Default")
      (node (ref "F3") (pin "1") (pinfunction "1_1") (pintype "passive"))
      (node (ref "U3") (pin "8") (pinfunction "GND_8") (pintype "power_in"))
    )
    (net (code "64") (name "Net-(U4-BOOT_0)") (class "Default")
      (node (ref "R11") (pin "2") (pinfunction "2_2") (pintype "passive"))
      (node (ref "U4") (pin "44") (pinfunction "BOOT_0_44") (pintype "passive"))
    )
    (net (code "65") (name "Net-(U4-PA2{slash}USART2_TX{slash}AIN2{slash}TIM2_CH3{slash}TIM15_CH1)") (class "Default")
      (node (ref "C98") (pin "2") (pinfunction "2_2") (pintype "passive"))
      (node (ref "R93") (pin "2") (pinfunction "2_2") (pintype "passive"))
      (node (ref "U4") (pin "12") (pinfunction "PA2/USART2_TX/AIN2/TIM2_CH3/TIM15_CH1_12") (pintype "passive"))
    )
    (net (code "66") (name "Net-(U4-~{NRST})") (class "Default")
      (node (ref "C6") (pin "1") (pinfunction "1_1") (pintype "passive"))
      (node (ref "U4") (pin "7") (pinfunction "~{NRST}_7") (pintype "passive"))
    )
    (net (code "67") (name "VIN") (class "Default")
      (node (ref "P4") (pin "1") (pinfunction "1_1") (pintype "passive"))
      (node (ref "R67") (pin "1") (pinfunction "1_1") (pintype "passive"))
      (node (ref "U3") (pin "9") (pinfunction "COM_9") (pintype "passive"))
    )
    (net (code "68") (name "unconnected-(U4-OSC32_OUT{slash}PC15-Pad4)") (class "Default")
      (node (ref "U4") (pin "4") (pinfunction "OSC32_OUT/PC15_4") (pintype "passive"))
    )
    (net (code "69") (name "unconnected-(U5-N{slash}C-Pad2)") (class "Default")
      (node (ref "U5") (pin "2") (pinfunction "N/C_2") (pintype "passive+no_connect"))
    )
    (net (code "70") (name "unconnected-(U5-RES-Pad10)") (class "Default")
      (node (ref "U5") (pin "10") (pinfunction "RES_10") (pintype "passive+no_connect"))
    )
  )
)
